# I-O_Connectors.net
KiCad netlist of a schematic drawn in Altium Designer
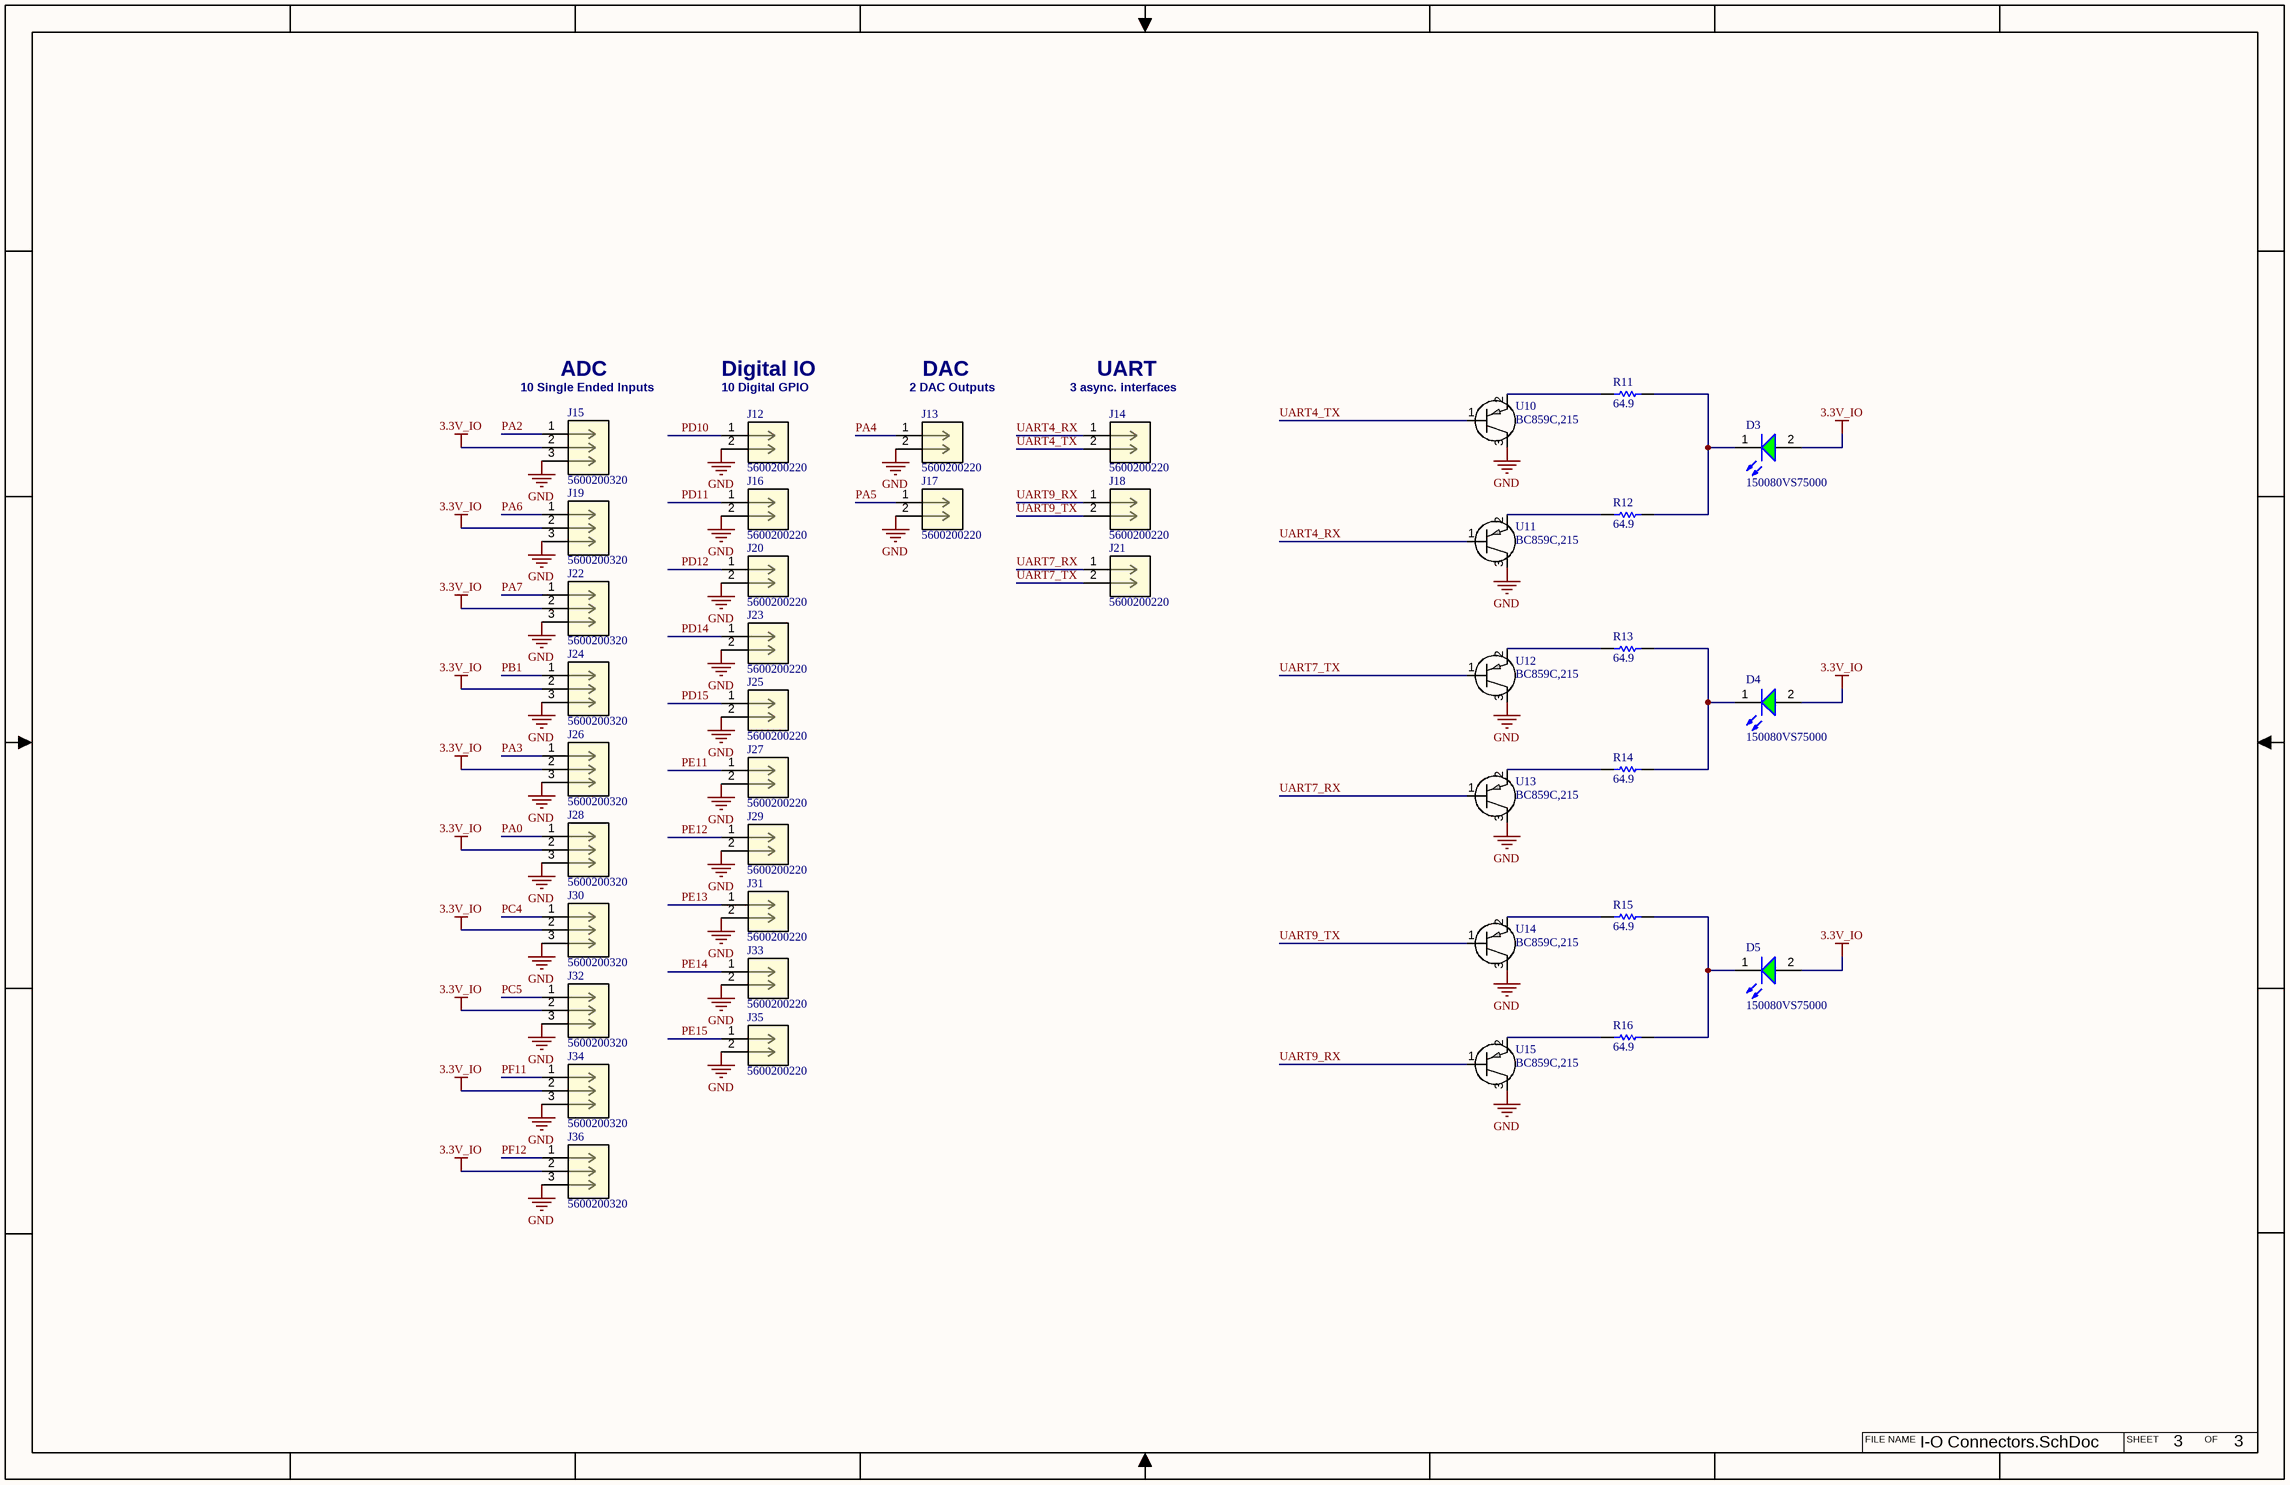
[diagram p0: I-O Connectors.SchDoc]

(export (version "E")
  (design (tool "Eeschema 10.0.6"))
  (components
    (comp (ref "D3")
      (value "150080VS75000")
      (footprint "WL-SMCW_0805_150080xx75000")
      (description "WL-SMCW SMT Mono-Color Chip LED Waterclear")
      (libsource (lib "Altium Content Vault") (part "LED_Green_2A-1K"))
    )
    (comp (ref "D4")
      (value "150080VS75000")
      (footprint "WL-SMCW_0805_150080xx75000")
      (description "WL-SMCW SMT Mono-Color Chip LED Waterclear")
      (libsource (lib "Altium Content Vault") (part "LED_Green_2A-1K"))
    )
    (comp (ref "D5")
      (value "150080VS75000")
      (footprint "WL-SMCW_0805_150080xx75000")
      (description "WL-SMCW SMT Mono-Color Chip LED Waterclear")
      (libsource (lib "Altium Content Vault") (part "LED_Green_2A-1K"))
    )
    (comp (ref "J12")
      (value "5600200220")
      (footprint "CONN_5600200220_MOL")
      (description "No Description Available")
      (libsource (lib "5600200220") (part "5600200220"))
    )
    (comp (ref "J13")
      (value "5600200220")
      (footprint "CONN_5600200220_MOL")
      (description "No Description Available")
      (libsource (lib "5600200220") (part "5600200220"))
    )
    (comp (ref "J14")
      (value "5600200220")
      (footprint "CONN_5600200220_MOL")
      (description "No Description Available")
      (libsource (lib "5600200220") (part "5600200220"))
    )
    (comp (ref "J15")
      (value "5600200320")
      (footprint "CONN03_560020_MOL")
      (description "No Description Available")
      (libsource (lib "5600200320") (part "5600200320"))
    )
    (comp (ref "J16")
      (value "5600200220")
      (footprint "CONN_5600200220_MOL")
      (description "No Description Available")
      (libsource (lib "5600200220") (part "5600200220"))
    )
    (comp (ref "J17")
      (value "5600200220")
      (footprint "CONN_5600200220_MOL")
      (description "No Description Available")
      (libsource (lib "5600200220") (part "5600200220"))
    )
    (comp (ref "J18")
      (value "5600200220")
      (footprint "CONN_5600200220_MOL")
      (description "No Description Available")
      (libsource (lib "5600200220") (part "5600200220"))
    )
    (comp (ref "J19")
      (value "5600200320")
      (footprint "CONN03_560020_MOL")
      (description "No Description Available")
      (libsource (lib "5600200320") (part "5600200320"))
    )
    (comp (ref "J20")
      (value "5600200220")
      (footprint "CONN_5600200220_MOL")
      (description "No Description Available")
      (libsource (lib "5600200220") (part "5600200220"))
    )
    (comp (ref "J21")
      (value "5600200220")
      (footprint "CONN_5600200220_MOL")
      (description "No Description Available")
      (libsource (lib "5600200220") (part "5600200220"))
    )
    (comp (ref "J22")
      (value "5600200320")
      (footprint "CONN03_560020_MOL")
      (description "No Description Available")
      (libsource (lib "5600200320") (part "5600200320"))
    )
    (comp (ref "J23")
      (value "5600200220")
      (footprint "CONN_5600200220_MOL")
      (description "No Description Available")
      (libsource (lib "5600200220") (part "5600200220"))
    )
    (comp (ref "J24")
      (value "5600200320")
      (footprint "CONN03_560020_MOL")
      (description "No Description Available")
      (libsource (lib "5600200320") (part "5600200320"))
    )
    (comp (ref "J25")
      (value "5600200220")
      (footprint "CONN_5600200220_MOL")
      (description "No Description Available")
      (libsource (lib "5600200220") (part "5600200220"))
    )
    (comp (ref "J26")
      (value "5600200320")
      (footprint "CONN03_560020_MOL")
      (description "No Description Available")
      (libsource (lib "5600200320") (part "5600200320"))
    )
    (comp (ref "J27")
      (value "5600200220")
      (footprint "CONN_5600200220_MOL")
      (description "No Description Available")
      (libsource (lib "5600200220") (part "5600200220"))
    )
    (comp (ref "J28")
      (value "5600200320")
      (footprint "CONN03_560020_MOL")
      (description "No Description Available")
      (libsource (lib "5600200320") (part "5600200320"))
    )
    (comp (ref "J29")
      (value "5600200220")
      (footprint "CONN_5600200220_MOL")
      (description "No Description Available")
      (libsource (lib "5600200220") (part "5600200220"))
    )
    (comp (ref "J30")
      (value "5600200320")
      (footprint "CONN03_560020_MOL")
      (description "No Description Available")
      (libsource (lib "5600200320") (part "5600200320"))
    )
    (comp (ref "J31")
      (value "5600200220")
      (footprint "CONN_5600200220_MOL")
      (description "No Description Available")
      (libsource (lib "5600200220") (part "5600200220"))
    )
    (comp (ref "J32")
      (value "5600200320")
      (footprint "CONN03_560020_MOL")
      (description "No Description Available")
      (libsource (lib "5600200320") (part "5600200320"))
    )
    (comp (ref "J33")
      (value "5600200220")
      (footprint "CONN_5600200220_MOL")
      (description "No Description Available")
      (libsource (lib "5600200220") (part "5600200220"))
    )
    (comp (ref "J34")
      (value "5600200320")
      (footprint "CONN03_560020_MOL")
      (description "No Description Available")
      (libsource (lib "5600200320") (part "5600200320"))
    )
    (comp (ref "J35")
      (value "5600200220")
      (footprint "CONN_5600200220_MOL")
      (description "No Description Available")
      (libsource (lib "5600200220") (part "5600200220"))
    )
    (comp (ref "J36")
      (value "5600200320")
      (footprint "CONN03_560020_MOL")
      (description "No Description Available")
      (libsource (lib "5600200320") (part "5600200320"))
    )
    (comp (ref "R11")
      (value "64.9")
      (footprint "RESC2013X60X35LL10T20")
      (fields (field (name "PART NUMBER") "RC0805FR-0764R9L") (field (name "MANUFACTURER") "Yageo"))
      (libsource (lib "Altium Content Vault") (part "RES"))
    )
    (comp (ref "R12")
      (value "64.9")
      (footprint "RESC2013X60X35LL10T20")
      (fields (field (name "PART NUMBER") "RC0805FR-0764R9L") (field (name "MANUFACTURER") "Yageo"))
      (libsource (lib "Altium Content Vault") (part "RES"))
    )
    (comp (ref "R13")
      (value "64.9")
      (footprint "RESC2013X60X35LL10T20")
      (fields (field (name "PART NUMBER") "RC0805FR-0764R9L") (field (name "MANUFACTURER") "Yageo"))
      (libsource (lib "Altium Content Vault") (part "RES"))
    )
    (comp (ref "R14")
      (value "64.9")
      (footprint "RESC2013X60X35LL10T20")
      (fields (field (name "PART NUMBER") "RC0805FR-0764R9L") (field (name "MANUFACTURER") "Yageo"))
      (libsource (lib "Altium Content Vault") (part "RES"))
    )
    (comp (ref "R15")
      (value "64.9")
      (footprint "RESC2013X60X35LL10T20")
      (fields (field (name "PART NUMBER") "RC0805FR-0764R9L") (field (name "MANUFACTURER") "Yageo"))
      (libsource (lib "Altium Content Vault") (part "RES"))
    )
    (comp (ref "R16")
      (value "64.9")
      (footprint "RESC2013X60X35LL10T20")
      (fields (field (name "PART NUMBER") "RC0805FR-0764R9L") (field (name "MANUFACTURER") "Yageo"))
      (libsource (lib "Altium Content Vault") (part "RES"))
    )
    (comp (ref "U10")
      (value "BC859C,215")
      (footprint "SOT23_NEX")
      (description "No Description Available")
      (libsource (lib "BC859C,215") (part "BC859C,215"))
    )
    (comp (ref "U11")
      (value "BC859C,215")
      (footprint "SOT23_NEX")
      (description "No Description Available")
      (libsource (lib "BC859C,215") (part "BC859C,215"))
    )
    (comp (ref "U12")
      (value "BC859C,215")
      (footprint "SOT23_NEX")
      (description "No Description Available")
      (libsource (lib "BC859C,215") (part "BC859C,215"))
    )
    (comp (ref "U13")
      (value "BC859C,215")
      (footprint "SOT23_NEX")
      (description "No Description Available")
      (libsource (lib "BC859C,215") (part "BC859C,215"))
    )
    (comp (ref "U14")
      (value "BC859C,215")
      (footprint "SOT23_NEX")
      (description "No Description Available")
      (libsource (lib "BC859C,215") (part "BC859C,215"))
    )
    (comp (ref "U15")
      (value "BC859C,215")
      (footprint "SOT23_NEX")
      (description "No Description Available")
      (libsource (lib "BC859C,215") (part "BC859C,215"))
    )
  )
  (nets
    (net (code "1") (name "/PA0") (class "Default")
      (node (ref "J28") (pin "1") (pinfunction "1_1") (pintype "passive"))
    )
    (net (code "2") (name "/PA2") (class "Default")
      (node (ref "J15") (pin "1") (pinfunction "1_1") (pintype "passive"))
    )
    (net (code "3") (name "/PA3") (class "Default")
      (node (ref "J26") (pin "1") (pinfunction "1_1") (pintype "passive"))
    )
    (net (code "4") (name "/PA4") (class "Default")
      (node (ref "J13") (pin "1") (pinfunction "1_1") (pintype "passive"))
    )
    (net (code "5") (name "/PA5") (class "Default")
      (node (ref "J17") (pin "1") (pinfunction "1_1") (pintype "passive"))
    )
    (net (code "6") (name "/PA6") (class "Default")
      (node (ref "J19") (pin "1") (pinfunction "1_1") (pintype "passive"))
    )
    (net (code "7") (name "/PA7") (class "Default")
      (node (ref "J22") (pin "1") (pinfunction "1_1") (pintype "passive"))
    )
    (net (code "8") (name "/PB1") (class "Default")
      (node (ref "J24") (pin "1") (pinfunction "1_1") (pintype "passive"))
    )
    (net (code "9") (name "/PC4") (class "Default")
      (node (ref "J30") (pin "1") (pinfunction "1_1") (pintype "passive"))
    )
    (net (code "10") (name "/PC5") (class "Default")
      (node (ref "J32") (pin "1") (pinfunction "1_1") (pintype "passive"))
    )
    (net (code "11") (name "/PD10") (class "Default")
      (node (ref "J12") (pin "1") (pinfunction "1_1") (pintype "passive"))
    )
    (net (code "12") (name "/PD11") (class "Default")
      (node (ref "J16") (pin "1") (pinfunction "1_1") (pintype "passive"))
    )
    (net (code "13") (name "/PD12") (class "Default")
      (node (ref "J20") (pin "1") (pinfunction "1_1") (pintype "passive"))
    )
    (net (code "14") (name "/PD14") (class "Default")
      (node (ref "J23") (pin "1") (pinfunction "1_1") (pintype "passive"))
    )
    (net (code "15") (name "/PD15") (class "Default")
      (node (ref "J25") (pin "1") (pinfunction "1_1") (pintype "passive"))
    )
    (net (code "16") (name "/PE11") (class "Default")
      (node (ref "J27") (pin "1") (pinfunction "1_1") (pintype "passive"))
    )
    (net (code "17") (name "/PE12") (class "Default")
      (node (ref "J29") (pin "1") (pinfunction "1_1") (pintype "passive"))
    )
    (net (code "18") (name "/PE13") (class "Default")
      (node (ref "J31") (pin "1") (pinfunction "1_1") (pintype "passive"))
    )
    (net (code "19") (name "/PE14") (class "Default")
      (node (ref "J33") (pin "1") (pinfunction "1_1") (pintype "passive"))
    )
    (net (code "20") (name "/PE15") (class "Default")
      (node (ref "J35") (pin "1") (pinfunction "1_1") (pintype "passive"))
    )
    (net (code "21") (name "/PF11") (class "Default")
      (node (ref "J34") (pin "1") (pinfunction "1_1") (pintype "passive"))
    )
    (net (code "22") (name "/PF12") (class "Default")
      (node (ref "J36") (pin "1") (pinfunction "1_1") (pintype "passive"))
    )
    (net (code "23") (name "/UART4_RX") (class "Default")
      (node (ref "J14") (pin "1") (pinfunction "1_1") (pintype "passive"))
      (node (ref "U11") (pin "1") (pinfunction "Base_1") (pintype "passive"))
    )
    (net (code "24") (name "/UART4_TX") (class "Default")
      (node (ref "J14") (pin "2") (pinfunction "2_2") (pintype "passive"))
      (node (ref "U10") (pin "1") (pinfunction "Base_1") (pintype "passive"))
    )
    (net (code "25") (name "/UART7_RX") (class "Default")
      (node (ref "J21") (pin "1") (pinfunction "1_1") (pintype "passive"))
      (node (ref "U13") (pin "1") (pinfunction "Base_1") (pintype "passive"))
    )
    (net (code "26") (name "/UART7_TX") (class "Default")
      (node (ref "J21") (pin "2") (pinfunction "2_2") (pintype "passive"))
      (node (ref "U12") (pin "1") (pinfunction "Base_1") (pintype "passive"))
    )
    (net (code "27") (name "/UART9_RX") (class "Default")
      (node (ref "J18") (pin "1") (pinfunction "1_1") (pintype "passive"))
      (node (ref "U15") (pin "1") (pinfunction "Base_1") (pintype "passive"))
    )
    (net (code "28") (name "/UART9_TX") (class "Default")
      (node (ref "J18") (pin "2") (pinfunction "2_2") (pintype "passive"))
      (node (ref "U14") (pin "1") (pinfunction "Base_1") (pintype "passive"))
    )
    (net (code "29") (name "3.3V_IO") (class "Default")
      (node (ref "D3") (pin "2") (pinfunction "A_2") (pintype "passive"))
      (node (ref "D4") (pin "2") (pinfunction "A_2") (pintype "passive"))
      (node (ref "D5") (pin "2") (pinfunction "A_2") (pintype "passive"))
      (node (ref "J15") (pin "2") (pinfunction "2_2") (pintype "passive"))
      (node (ref "J19") (pin "2") (pinfunction "2_2") (pintype "passive"))
      (node (ref "J22") (pin "2") (pinfunction "2_2") (pintype "passive"))
      (node (ref "J24") (pin "2") (pinfunction "2_2") (pintype "passive"))
      (node (ref "J26") (pin "2") (pinfunction "2_2") (pintype "passive"))
      (node (ref "J28") (pin "2") (pinfunction "2_2") (pintype "passive"))
      (node (ref "J30") (pin "2") (pinfunction "2_2") (pintype "passive"))
      (node (ref "J32") (pin "2") (pinfunction "2_2") (pintype "passive"))
      (node (ref "J34") (pin "2") (pinfunction "2_2") (pintype "passive"))
      (node (ref "J36") (pin "2") (pinfunction "2_2") (pintype "passive"))
    )
    (net (code "30") (name "GND") (class "Default")
      (node (ref "J12") (pin "2") (pinfunction "2_2") (pintype "passive"))
      (node (ref "J13") (pin "2") (pinfunction "2_2") (pintype "passive"))
      (node (ref "J15") (pin "3") (pinfunction "3_3") (pintype "passive"))
      (node (ref "J16") (pin "2") (pinfunction "2_2") (pintype "passive"))
      (node (ref "J17") (pin "2") (pinfunction "2_2") (pintype "passive"))
      (node (ref "J19") (pin "3") (pinfunction "3_3") (pintype "passive"))
      (node (ref "J20") (pin "2") (pinfunction "2_2") (pintype "passive"))
      (node (ref "J22") (pin "3") (pinfunction "3_3") (pintype "passive"))
      (node (ref "J23") (pin "2") (pinfunction "2_2") (pintype "passive"))
      (node (ref "J24") (pin "3") (pinfunction "3_3") (pintype "passive"))
      (node (ref "J25") (pin "2") (pinfunction "2_2") (pintype "passive"))
      (node (ref "J26") (pin "3") (pinfunction "3_3") (pintype "passive"))
      (node (ref "J27") (pin "2") (pinfunction "2_2") (pintype "passive"))
      (node (ref "J28") (pin "3") (pinfunction "3_3") (pintype "passive"))
      (node (ref "J29") (pin "2") (pinfunction "2_2") (pintype "passive"))
      (node (ref "J30") (pin "3") (pinfunction "3_3") (pintype "passive"))
      (node (ref "J31") (pin "2") (pinfunction "2_2") (pintype "passive"))
      (node (ref "J32") (pin "3") (pinfunction "3_3") (pintype "passive"))
      (node (ref "J33") (pin "2") (pinfunction "2_2") (pintype "passive"))
      (node (ref "J34") (pin "3") (pinfunction "3_3") (pintype "passive"))
      (node (ref "J35") (pin "2") (pinfunction "2_2") (pintype "passive"))
      (node (ref "J36") (pin "3") (pinfunction "3_3") (pintype "passive"))
      (node (ref "U10") (pin "3") (pinfunction "Collector_3") (pintype "passive"))
      (node (ref "U11") (pin "3") (pinfunction "Collector_3") (pintype "passive"))
      (node (ref "U12") (pin "3") (pinfunction "Collector_3") (pintype "passive"))
      (node (ref "U13") (pin "3") (pinfunction "Collector_3") (pintype "passive"))
      (node (ref "U14") (pin "3") (pinfunction "Collector_3") (pintype "passive"))
      (node (ref "U15") (pin "3") (pinfunction "Collector_3") (pintype "passive"))
    )
    (net (code "31") (name "Net-(D3-K)") (class "Default")
      (node (ref "D3") (pin "1") (pinfunction "K_1") (pintype "passive"))
      (node (ref "R11") (pin "1") (pinfunction "1_1") (pintype "passive"))
      (node (ref "R12") (pin "1") (pinfunction "1_1") (pintype "passive"))
    )
    (net (code "32") (name "Net-(D4-K)") (class "Default")
      (node (ref "D4") (pin "1") (pinfunction "K_1") (pintype "passive"))
      (node (ref "R13") (pin "1") (pinfunction "1_1") (pintype "passive"))
      (node (ref "R14") (pin "1") (pinfunction "1_1") (pintype "passive"))
    )
    (net (code "33") (name "Net-(D5-K)") (class "Default")
      (node (ref "D5") (pin "1") (pinfunction "K_1") (pintype "passive"))
      (node (ref "R15") (pin "1") (pinfunction "1_1") (pintype "passive"))
      (node (ref "R16") (pin "1") (pinfunction "1_1") (pintype "passive"))
    )
    (net (code "34") (name "Net-(U10-Emitter)") (class "Default")
      (node (ref "R11") (pin "2") (pinfunction "2_2") (pintype "passive"))
      (node (ref "U10") (pin "2") (pinfunction "Emitter_2") (pintype "passive"))
    )
    (net (code "35") (name "Net-(U11-Emitter)") (class "Default")
      (node (ref "R12") (pin "2") (pinfunction "2_2") (pintype "passive"))
      (node (ref "U11") (pin "2") (pinfunction "Emitter_2") (pintype "passive"))
    )
    (net (code "36") (name "Net-(U12-Emitter)") (class "Default")
      (node (ref "R13") (pin "2") (pinfunction "2_2") (pintype "passive"))
      (node (ref "U12") (pin "2") (pinfunction "Emitter_2") (pintype "passive"))
    )
    (net (code "37") (name "Net-(U13-Emitter)") (class "Default")
      (node (ref "R14") (pin "2") (pinfunction "2_2") (pintype "passive"))
      (node (ref "U13") (pin "2") (pinfunction "Emitter_2") (pintype "passive"))
    )
    (net (code "38") (name "Net-(U14-Emitter)") (class "Default")
      (node (ref "R15") (pin "2") (pinfunction "2_2") (pintype "passive"))
      (node (ref "U14") (pin "2") (pinfunction "Emitter_2") (pintype "passive"))
    )
    (net (code "39") (name "Net-(U15-Emitter)") (class "Default")
      (node (ref "R16") (pin "2") (pinfunction "2_2") (pintype "passive"))
      (node (ref "U15") (pin "2") (pinfunction "Emitter_2") (pintype "passive"))
    )
  )
)
